# cherrymx_rgb_breakout.net
KiCad netlist of a schematic drawn in EAGLE
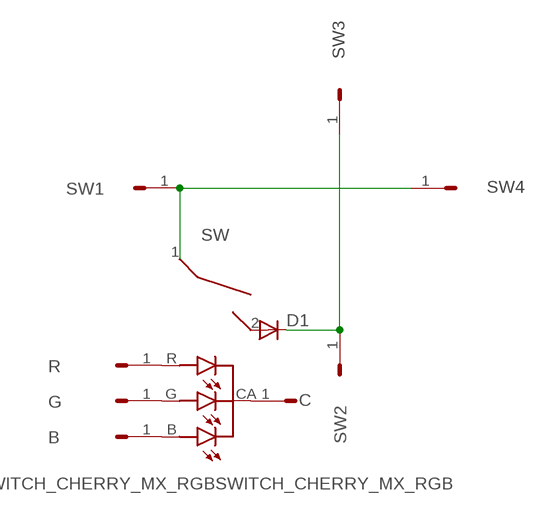
[diagram p0: schematic, sheet 1]

(export (version "E")
  (design (tool "Eeschema 10.0.6"))
  (components
    (comp (ref "B")
      (value "HEADER/MALE/01")
      (footprint "eagle-import:HEADER_MALE_01")
      (libsource (lib "eagle-import") (part "HEADER/MALE/01"))
    )
    (comp (ref "C")
      (value "HEADER/MALE/01")
      (footprint "eagle-import:HEADER_MALE_01")
      (libsource (lib "eagle-import") (part "HEADER/MALE/01"))
    )
    (comp (ref "D1")
      (value "1N4148DO35-7")
      (footprint "eagle-import:DO35-7")
      (libsource (lib "eagle-import") (part "1N4148DO35-7"))
    )
    (comp (ref "G")
      (value "HEADER/MALE/01")
      (footprint "eagle-import:HEADER_MALE_01")
      (libsource (lib "eagle-import") (part "HEADER/MALE/01"))
    )
    (comp (ref "R")
      (value "HEADER/MALE/01")
      (footprint "eagle-import:HEADER_MALE_01")
      (libsource (lib "eagle-import") (part "HEADER/MALE/01"))
    )
    (comp (ref "SW")
      (value "SWITCH_CHERRY_MX_RGBSWITCH_CHERRY_MX_RGB")
      (footprint "eagle-import:SWITCH_CHERRY_MX_RGB")
      (libsource (lib "eagle-import") (part "SWITCH_CHERRY_MX_RGBSWITCH_CHERRY_MX_RGB"))
    )
    (comp (ref "SW1")
      (value "HEADER/MALE/01")
      (footprint "eagle-import:HEADER_MALE_01")
      (libsource (lib "eagle-import") (part "HEADER/MALE/01"))
    )
    (comp (ref "SW2")
      (value "HEADER/MALE/01")
      (footprint "eagle-import:HEADER_MALE_01")
      (libsource (lib "eagle-import") (part "HEADER/MALE/01"))
    )
    (comp (ref "SW3")
      (value "HEADER/MALE/01")
      (footprint "eagle-import:HEADER_MALE_01")
      (libsource (lib "eagle-import") (part "HEADER/MALE/01"))
    )
    (comp (ref "SW4")
      (value "HEADER/MALE/01")
      (footprint "eagle-import:HEADER_MALE_01")
      (libsource (lib "eagle-import") (part "HEADER/MALE/01"))
    )
  )
  (nets
    (net (code "1") (name "Net-(B-3)") (class "Default")
      (node (ref "B") (pin "1") (pinfunction "3_1") (pintype "passive"))
      (node (ref "SW") (pin "B") (pinfunction "B-CAT_B") (pintype "passive"))
    )
    (net (code "2") (name "Net-(C-3)") (class "Default")
      (node (ref "C") (pin "1") (pinfunction "3_1") (pintype "passive"))
      (node (ref "SW") (pin "CA") (pinfunction "COMMON-ANODE_CA") (pintype "passive"))
    )
    (net (code "3") (name "Net-(D1-PadA)") (class "Default")
      (node (ref "D1") (pin "A") (pinfunction "A_A") (pintype "passive"))
      (node (ref "SW") (pin "2") (pinfunction "2_2") (pintype "passive"))
    )
    (net (code "4") (name "Net-(G-3)") (class "Default")
      (node (ref "G") (pin "1") (pinfunction "3_1") (pintype "passive"))
      (node (ref "SW") (pin "G") (pinfunction "G-CAT_G") (pintype "passive"))
    )
    (net (code "5") (name "Net-(R-3)") (class "Default")
      (node (ref "R") (pin "1") (pinfunction "3_1") (pintype "passive"))
      (node (ref "SW") (pin "R") (pinfunction "R-CAT_R") (pintype "passive"))
    )
    (net (code "6") (name "Net-(SW1-3)") (class "Default")
      (node (ref "SW") (pin "1") (pinfunction "1_1") (pintype "passive"))
      (node (ref "SW1") (pin "1") (pinfunction "3_1") (pintype "passive"))
      (node (ref "SW4") (pin "1") (pinfunction "3_1") (pintype "passive"))
    )
    (net (code "7") (name "Net-(SW2-3)") (class "Default")
      (node (ref "D1") (pin "C") (pinfunction "C_C") (pintype "passive"))
      (node (ref "SW2") (pin "1") (pinfunction "3_1") (pintype "passive"))
      (node (ref "SW3") (pin "1") (pinfunction "3_1") (pintype "passive"))
    )
  )
)
